# Manchester.net
KiCad netlist of a schematic drawn in Altium Designer
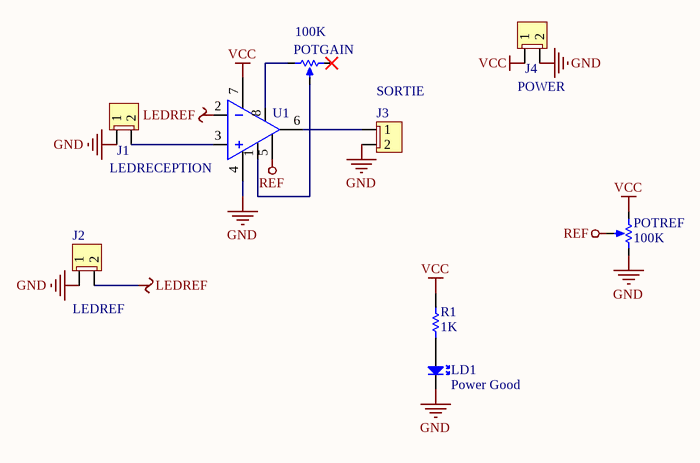
[diagram p0: Manchester.SchDoc]

(export (version "E")
  (design (tool "Eeschema 10.0.6"))
  (components
    (comp (ref "J1")
      (value "Input")
      (footprint "MTA100-2")
      (description "MTA Male 0 Degres")
      (fields (field (name "CONNECTOR TYPE") "LEDRECEPTION"))
      (libsource (lib "Lib Sch") (part "MTA100-2"))
    )
    (comp (ref "J2")
      (value "Input")
      (footprint "MTA100-2")
      (description "MTA Male 0 Degres")
      (fields (field (name "CONNECTOR TYPE") "LEDREF"))
      (libsource (lib "Lib Sch") (part "MTA100-2"))
    )
    (comp (ref "J3")
      (value "Input")
      (footprint "MTA100-2")
      (description "MTA Male 0 Degres")
      (fields (field (name "CONNECTOR TYPE") "SORTIE"))
      (libsource (lib "") (part "MTA100-2_1"))
    )
    (comp (ref "J4")
      (value "Input")
      (footprint "MTA100-2")
      (description "MTA Male 0 Degres")
      (fields (field (name "CONNECTOR TYPE") "POWER"))
      (libsource (lib "Lib Sch") (part "MTA100-2"))
    )
    (comp (ref "LD1")
      (value "Power Good")
      (footprint "LED 3mm Vertical")
      (description "Through Hole")
      (fields (field (name "PUBLISHER") "Altium Limited"))
      (libsource (lib "Lib Sch") (part "LED 3mm Vertical"))
    )
    (comp (ref "POTGAIN")
      (value "100K")
      (footprint "VR1")
      (fields (field (name "Comment") "?????"))
      (libsource (lib "Lib Sch") (part "Res Pot 10T Vertical"))
    )
    (comp (ref "POTREF")
      (value "100K")
      (footprint "VR1")
      (fields (field (name "Comment") "?????"))
      (libsource (lib "Lib Sch") (part "Res Pot 10T Vertical"))
    )
    (comp (ref "R1")
      (value "1K")
      (footprint "Axial 0.4\" Step")
      (description "Resistor")
      (fields (field (name "Comment") "Res 1/4W") (field (name "PUBLISHER") "Altium Limited"))
      (libsource (lib "Lib Sch") (part "Res 1/4W"))
    )
    (comp (ref "U1")
      (value "OpAmp Single")
      (footprint "DIP8")
      (libsource (lib "Lib Sch") (part "OpAmp Single"))
    )
  )
  (nets
    (net (code "1") (name "GND") (class "Default")
      (node (ref "J1") (pin "1") (pinfunction "1_1") (pintype "passive"))
      (node (ref "J2") (pin "1") (pinfunction "1_1") (pintype "passive"))
      (node (ref "J3") (pin "2") (pinfunction "2_2") (pintype "passive"))
      (node (ref "J4") (pin "2") (pinfunction "2_2") (pintype "passive"))
      (node (ref "LD1") (pin "2") (pinfunction "K_2") (pintype "passive"))
      (node (ref "POTREF") (pin "3") (pinfunction "Bot_3") (pintype "passive"))
      (node (ref "U1") (pin "4") (pinfunction "-Vcc_4") (pintype "passive"))
    )
    (net (code "2") (name "LEDREF") (class "Default")
      (node (ref "J2") (pin "2") (pinfunction "2_2") (pintype "passive"))
      (node (ref "U1") (pin "2") (pinfunction "-_2") (pintype "passive"))
    )
    (net (code "3") (name "Net-(LD1-A)") (class "Default")
      (node (ref "LD1") (pin "1") (pinfunction "A_1") (pintype "passive"))
      (node (ref "R1") (pin "2") (pinfunction "2_2") (pintype "passive"))
    )
    (net (code "4") (name "Net-(POTGAIN-Tap)") (class "Default")
      (node (ref "POTGAIN") (pin "2") (pinfunction "Tap_2") (pintype "passive"))
      (node (ref "U1") (pin "1") (pinfunction "B_1") (pintype "passive"))
    )
    (net (code "5") (name "Net-(POTGAIN-Top)") (class "Default")
      (node (ref "POTGAIN") (pin "1") (pinfunction "Top_1") (pintype "passive"))
      (node (ref "U1") (pin "8") (pinfunction "NC_8") (pintype "passive"))
    )
    (net (code "6") (name "Net-(U1-+)") (class "Default")
      (node (ref "J1") (pin "2") (pinfunction "2_2") (pintype "passive"))
      (node (ref "U1") (pin "3") (pinfunction "+_3") (pintype "passive"))
    )
    (net (code "7") (name "Net-(U1-Out)") (class "Default")
      (node (ref "J3") (pin "1") (pinfunction "1_1") (pintype "passive"))
      (node (ref "U1") (pin "6") (pinfunction "Out_6") (pintype "passive"))
    )
    (net (code "8") (name "REF") (class "Default")
      (node (ref "POTREF") (pin "2") (pinfunction "Tap_2") (pintype "passive"))
      (node (ref "U1") (pin "5") (pinfunction "B_5") (pintype "passive"))
    )
    (net (code "9") (name "VCC") (class "Default")
      (node (ref "J4") (pin "1") (pinfunction "1_1") (pintype "passive"))
      (node (ref "POTREF") (pin "1") (pinfunction "Top_1") (pintype "passive"))
      (node (ref "R1") (pin "1") (pinfunction "1_1") (pintype "passive"))
      (node (ref "U1") (pin "7") (pinfunction "+Vcc_7") (pintype "passive"))
    )
    (net (code "10") (name "unconnected-(POTGAIN-Bot-Pad3)") (class "Default")
      (node (ref "POTGAIN") (pin "3") (pinfunction "Bot_3") (pintype "passive+no_connect"))
    )
  )
)
